# 2layer_v1.net
KiCad netlist of a schematic drawn in EAGLE
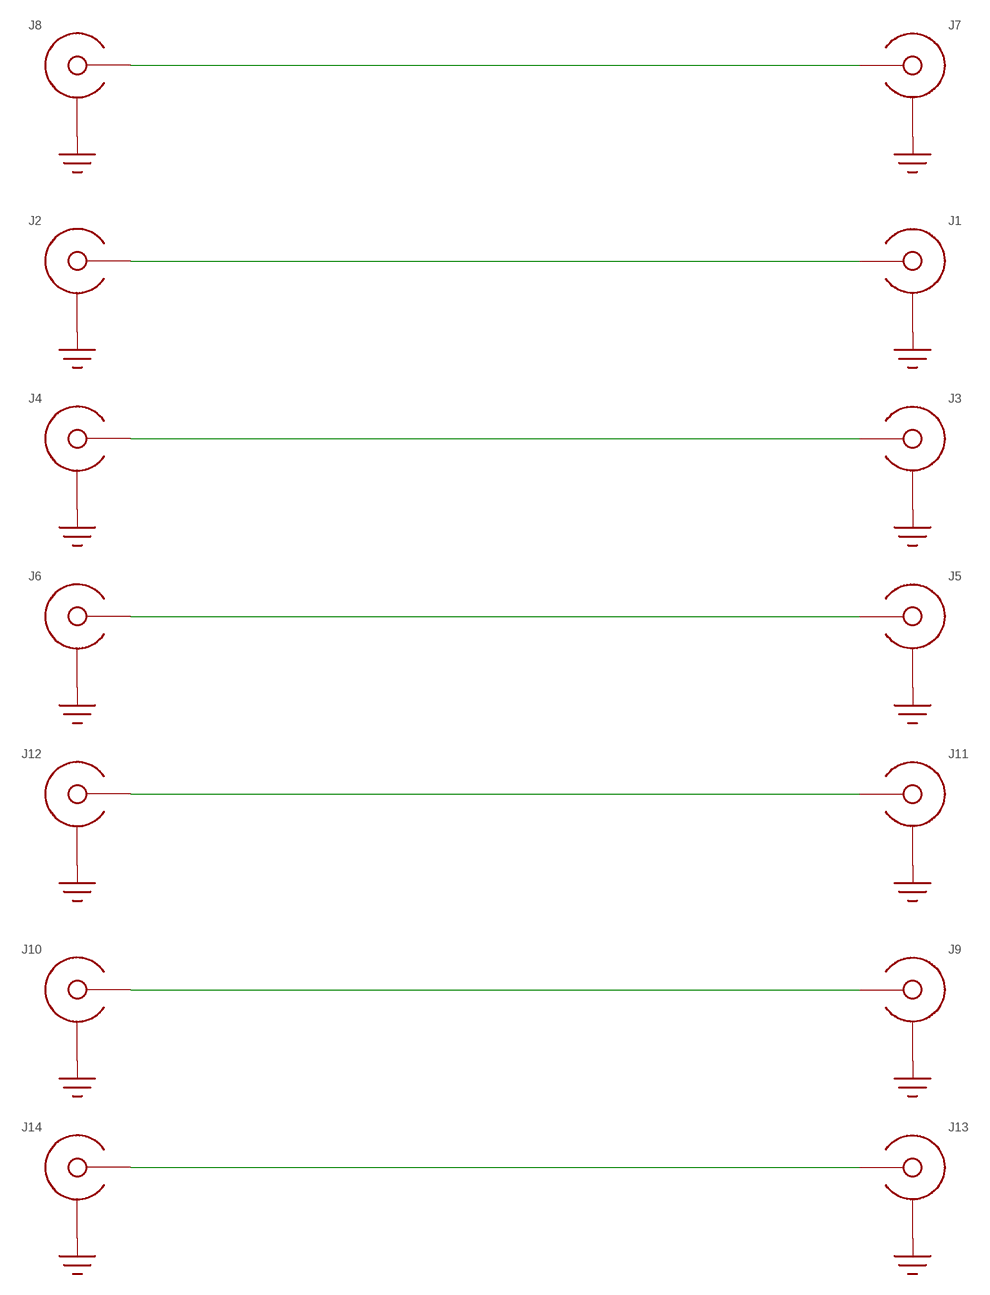
[diagram p0: schematic, sheet 1]

(export (version "E")
  (design (tool "Eeschema 10.0.6"))
  (components
    (comp (ref "J1")
      (value "SMA_END_LAUNCH2L")
      (footprint "eagle-import:SMA_EDGE_LAUNCH_2L")
      (libsource (lib "eagle-import") (part "SMA_END_LAUNCH2L"))
    )
    (comp (ref "J2")
      (value "SMA_END_LAUNCH2L")
      (footprint "eagle-import:SMA_EDGE_LAUNCH_2L")
      (libsource (lib "eagle-import") (part "SMA_END_LAUNCH2L"))
    )
    (comp (ref "J3")
      (value "SMA_END_LAUNCH2L")
      (footprint "eagle-import:SMA_EDGE_LAUNCH_2L")
      (libsource (lib "eagle-import") (part "SMA_END_LAUNCH2L"))
    )
    (comp (ref "J4")
      (value "SMA_END_LAUNCH2L")
      (footprint "eagle-import:SMA_EDGE_LAUNCH_2L")
      (libsource (lib "eagle-import") (part "SMA_END_LAUNCH2L"))
    )
    (comp (ref "J5")
      (value "SMA_END_LAUNCH2L")
      (footprint "eagle-import:SMA_EDGE_LAUNCH_2L")
      (libsource (lib "eagle-import") (part "SMA_END_LAUNCH2L"))
    )
    (comp (ref "J6")
      (value "SMA_END_LAUNCH2L")
      (footprint "eagle-import:SMA_EDGE_LAUNCH_2L")
      (libsource (lib "eagle-import") (part "SMA_END_LAUNCH2L"))
    )
    (comp (ref "J7")
      (value "SMA_END_LAUNCH2L")
      (footprint "eagle-import:SMA_EDGE_LAUNCH_2L")
      (libsource (lib "eagle-import") (part "SMA_END_LAUNCH2L"))
    )
    (comp (ref "J8")
      (value "SMA_END_LAUNCH2L")
      (footprint "eagle-import:SMA_EDGE_LAUNCH_2L")
      (libsource (lib "eagle-import") (part "SMA_END_LAUNCH2L"))
    )
    (comp (ref "J9")
      (value "SMA_END_LAUNCH2L")
      (footprint "eagle-import:SMA_EDGE_LAUNCH_2L")
      (libsource (lib "eagle-import") (part "SMA_END_LAUNCH2L"))
    )
    (comp (ref "J10")
      (value "SMA_END_LAUNCH2L")
      (footprint "eagle-import:SMA_EDGE_LAUNCH_2L")
      (libsource (lib "eagle-import") (part "SMA_END_LAUNCH2L"))
    )
    (comp (ref "J11")
      (value "SMA_END_LAUNCH2L")
      (footprint "eagle-import:SMA_EDGE_LAUNCH_2L")
      (libsource (lib "eagle-import") (part "SMA_END_LAUNCH2L"))
    )
    (comp (ref "J12")
      (value "SMA_END_LAUNCH2L")
      (footprint "eagle-import:SMA_EDGE_LAUNCH_2L")
      (libsource (lib "eagle-import") (part "SMA_END_LAUNCH2L"))
    )
    (comp (ref "J13")
      (value "SMA_END_LAUNCH2L")
      (footprint "eagle-import:SMA_EDGE_LAUNCH_2L")
      (libsource (lib "eagle-import") (part "SMA_END_LAUNCH2L"))
    )
    (comp (ref "J14")
      (value "SMA_END_LAUNCH2L")
      (footprint "eagle-import:SMA_EDGE_LAUNCH_2L")
      (libsource (lib "eagle-import") (part "SMA_END_LAUNCH2L"))
    )
  )
  (nets
    (net (code "1") (name "GND") (class "Default")
      (node (ref "J1") (pin "BOTTOM_GND") (pinfunction "SHIELD_BOTTOM_GND") (pintype "bidirectional"))
      (node (ref "J1") (pin "GND@1") (pinfunction "SHIELD_GND@1") (pintype "bidirectional"))
      (node (ref "J1") (pin "GND@11") (pinfunction "SHIELD_GND@11") (pintype "bidirectional"))
      (node (ref "J1") (pin "GND@12") (pinfunction "SHIELD_GND@12") (pintype "bidirectional"))
      (node (ref "J1") (pin "GND@14") (pinfunction "SHIELD_GND@14") (pintype "bidirectional"))
      (node (ref "J1") (pin "GND@15") (pinfunction "SHIELD_GND@15") (pintype "bidirectional"))
      (node (ref "J1") (pin "GND@16") (pinfunction "SHIELD_GND@16") (pintype "bidirectional"))
      (node (ref "J1") (pin "GND@17") (pinfunction "SHIELD_GND@17") (pintype "bidirectional"))
      (node (ref "J1") (pin "GND@2") (pinfunction "SHIELD_GND@2") (pintype "bidirectional"))
      (node (ref "J1") (pin "GND@3") (pinfunction "SHIELD_GND@3") (pintype "bidirectional"))
      (node (ref "J1") (pin "GND@4") (pinfunction "SHIELD_GND@4") (pintype "bidirectional"))
      (node (ref "J1") (pin "GND@5") (pinfunction "SHIELD_GND@5") (pintype "bidirectional"))
      (node (ref "J1") (pin "GND@6") (pinfunction "SHIELD_GND@6") (pintype "bidirectional"))
      (node (ref "J1") (pin "GND@7") (pinfunction "SHIELD_GND@7") (pintype "bidirectional"))
      (node (ref "J1") (pin "GND@8") (pinfunction "SHIELD_GND@8") (pintype "bidirectional"))
      (node (ref "J1") (pin "GND_PAD1") (pinfunction "SHIELD_GND_PAD1") (pintype "bidirectional"))
      (node (ref "J1") (pin "GND_PAD2") (pinfunction "SHIELD_GND_PAD2") (pintype "bidirectional"))
      (node (ref "J10") (pin "BOTTOM_GND") (pinfunction "SHIELD_BOTTOM_GND") (pintype "bidirectional"))
      (node (ref "J10") (pin "GND@1") (pinfunction "SHIELD_GND@1") (pintype "bidirectional"))
      (node (ref "J10") (pin "GND@11") (pinfunction "SHIELD_GND@11") (pintype "bidirectional"))
      (node (ref "J10") (pin "GND@12") (pinfunction "SHIELD_GND@12") (pintype "bidirectional"))
      (node (ref "J10") (pin "GND@14") (pinfunction "SHIELD_GND@14") (pintype "bidirectional"))
      (node (ref "J10") (pin "GND@15") (pinfunction "SHIELD_GND@15") (pintype "bidirectional"))
      (node (ref "J10") (pin "GND@16") (pinfunction "SHIELD_GND@16") (pintype "bidirectional"))
      (node (ref "J10") (pin "GND@17") (pinfunction "SHIELD_GND@17") (pintype "bidirectional"))
      (node (ref "J10") (pin "GND@2") (pinfunction "SHIELD_GND@2") (pintype "bidirectional"))
      (node (ref "J10") (pin "GND@3") (pinfunction "SHIELD_GND@3") (pintype "bidirectional"))
      (node (ref "J10") (pin "GND@4") (pinfunction "SHIELD_GND@4") (pintype "bidirectional"))
      (node (ref "J10") (pin "GND@5") (pinfunction "SHIELD_GND@5") (pintype "bidirectional"))
      (node (ref "J10") (pin "GND@6") (pinfunction "SHIELD_GND@6") (pintype "bidirectional"))
      (node (ref "J10") (pin "GND@7") (pinfunction "SHIELD_GND@7") (pintype "bidirectional"))
      (node (ref "J10") (pin "GND@8") (pinfunction "SHIELD_GND@8") (pintype "bidirectional"))
      (node (ref "J10") (pin "GND_PAD1") (pinfunction "SHIELD_GND_PAD1") (pintype "bidirectional"))
      (node (ref "J10") (pin "GND_PAD2") (pinfunction "SHIELD_GND_PAD2") (pintype "bidirectional"))
      (node (ref "J11") (pin "BOTTOM_GND") (pinfunction "SHIELD_BOTTOM_GND") (pintype "bidirectional"))
      (node (ref "J11") (pin "GND@1") (pinfunction "SHIELD_GND@1") (pintype "bidirectional"))
      (node (ref "J11") (pin "GND@11") (pinfunction "SHIELD_GND@11") (pintype "bidirectional"))
      (node (ref "J11") (pin "GND@12") (pinfunction "SHIELD_GND@12") (pintype "bidirectional"))
      (node (ref "J11") (pin "GND@14") (pinfunction "SHIELD_GND@14") (pintype "bidirectional"))
      (node (ref "J11") (pin "GND@15") (pinfunction "SHIELD_GND@15") (pintype "bidirectional"))
      (node (ref "J11") (pin "GND@16") (pinfunction "SHIELD_GND@16") (pintype "bidirectional"))
      (node (ref "J11") (pin "GND@17") (pinfunction "SHIELD_GND@17") (pintype "bidirectional"))
      (node (ref "J11") (pin "GND@2") (pinfunction "SHIELD_GND@2") (pintype "bidirectional"))
      (node (ref "J11") (pin "GND@3") (pinfunction "SHIELD_GND@3") (pintype "bidirectional"))
      (node (ref "J11") (pin "GND@4") (pinfunction "SHIELD_GND@4") (pintype "bidirectional"))
      (node (ref "J11") (pin "GND@5") (pinfunction "SHIELD_GND@5") (pintype "bidirectional"))
      (node (ref "J11") (pin "GND@6") (pinfunction "SHIELD_GND@6") (pintype "bidirectional"))
      (node (ref "J11") (pin "GND@7") (pinfunction "SHIELD_GND@7") (pintype "bidirectional"))
      (node (ref "J11") (pin "GND@8") (pinfunction "SHIELD_GND@8") (pintype "bidirectional"))
      (node (ref "J11") (pin "GND_PAD1") (pinfunction "SHIELD_GND_PAD1") (pintype "bidirectional"))
      (node (ref "J11") (pin "GND_PAD2") (pinfunction "SHIELD_GND_PAD2") (pintype "bidirectional"))
      (node (ref "J12") (pin "BOTTOM_GND") (pinfunction "SHIELD_BOTTOM_GND") (pintype "bidirectional"))
      (node (ref "J12") (pin "GND@1") (pinfunction "SHIELD_GND@1") (pintype "bidirectional"))
      (node (ref "J12") (pin "GND@11") (pinfunction "SHIELD_GND@11") (pintype "bidirectional"))
      (node (ref "J12") (pin "GND@12") (pinfunction "SHIELD_GND@12") (pintype "bidirectional"))
      (node (ref "J12") (pin "GND@14") (pinfunction "SHIELD_GND@14") (pintype "bidirectional"))
      (node (ref "J12") (pin "GND@15") (pinfunction "SHIELD_GND@15") (pintype "bidirectional"))
      (node (ref "J12") (pin "GND@16") (pinfunction "SHIELD_GND@16") (pintype "bidirectional"))
      (node (ref "J12") (pin "GND@17") (pinfunction "SHIELD_GND@17") (pintype "bidirectional"))
      (node (ref "J12") (pin "GND@2") (pinfunction "SHIELD_GND@2") (pintype "bidirectional"))
      (node (ref "J12") (pin "GND@3") (pinfunction "SHIELD_GND@3") (pintype "bidirectional"))
      (node (ref "J12") (pin "GND@4") (pinfunction "SHIELD_GND@4") (pintype "bidirectional"))
      (node (ref "J12") (pin "GND@5") (pinfunction "SHIELD_GND@5") (pintype "bidirectional"))
      (node (ref "J12") (pin "GND@6") (pinfunction "SHIELD_GND@6") (pintype "bidirectional"))
      (node (ref "J12") (pin "GND@7") (pinfunction "SHIELD_GND@7") (pintype "bidirectional"))
      (node (ref "J12") (pin "GND@8") (pinfunction "SHIELD_GND@8") (pintype "bidirectional"))
      (node (ref "J12") (pin "GND_PAD1") (pinfunction "SHIELD_GND_PAD1") (pintype "bidirectional"))
      (node (ref "J12") (pin "GND_PAD2") (pinfunction "SHIELD_GND_PAD2") (pintype "bidirectional"))
      (node (ref "J13") (pin "BOTTOM_GND") (pinfunction "SHIELD_BOTTOM_GND") (pintype "bidirectional"))
      (node (ref "J13") (pin "GND@1") (pinfunction "SHIELD_GND@1") (pintype "bidirectional"))
      (node (ref "J13") (pin "GND@11") (pinfunction "SHIELD_GND@11") (pintype "bidirectional"))
      (node (ref "J13") (pin "GND@12") (pinfunction "SHIELD_GND@12") (pintype "bidirectional"))
      (node (ref "J13") (pin "GND@14") (pinfunction "SHIELD_GND@14") (pintype "bidirectional"))
      (node (ref "J13") (pin "GND@15") (pinfunction "SHIELD_GND@15") (pintype "bidirectional"))
      (node (ref "J13") (pin "GND@16") (pinfunction "SHIELD_GND@16") (pintype "bidirectional"))
      (node (ref "J13") (pin "GND@17") (pinfunction "SHIELD_GND@17") (pintype "bidirectional"))
      (node (ref "J13") (pin "GND@2") (pinfunction "SHIELD_GND@2") (pintype "bidirectional"))
      (node (ref "J13") (pin "GND@3") (pinfunction "SHIELD_GND@3") (pintype "bidirectional"))
      (node (ref "J13") (pin "GND@4") (pinfunction "SHIELD_GND@4") (pintype "bidirectional"))
      (node (ref "J13") (pin "GND@5") (pinfunction "SHIELD_GND@5") (pintype "bidirectional"))
      (node (ref "J13") (pin "GND@6") (pinfunction "SHIELD_GND@6") (pintype "bidirectional"))
      (node (ref "J13") (pin "GND@7") (pinfunction "SHIELD_GND@7") (pintype "bidirectional"))
      (node (ref "J13") (pin "GND@8") (pinfunction "SHIELD_GND@8") (pintype "bidirectional"))
      (node (ref "J13") (pin "GND_PAD1") (pinfunction "SHIELD_GND_PAD1") (pintype "bidirectional"))
      (node (ref "J13") (pin "GND_PAD2") (pinfunction "SHIELD_GND_PAD2") (pintype "bidirectional"))
      (node (ref "J14") (pin "BOTTOM_GND") (pinfunction "SHIELD_BOTTOM_GND") (pintype "bidirectional"))
      (node (ref "J14") (pin "GND@1") (pinfunction "SHIELD_GND@1") (pintype "bidirectional"))
      (node (ref "J14") (pin "GND@11") (pinfunction "SHIELD_GND@11") (pintype "bidirectional"))
      (node (ref "J14") (pin "GND@12") (pinfunction "SHIELD_GND@12") (pintype "bidirectional"))
      (node (ref "J14") (pin "GND@14") (pinfunction "SHIELD_GND@14") (pintype "bidirectional"))
      (node (ref "J14") (pin "GND@15") (pinfunction "SHIELD_GND@15") (pintype "bidirectional"))
      (node (ref "J14") (pin "GND@16") (pinfunction "SHIELD_GND@16") (pintype "bidirectional"))
      (node (ref "J14") (pin "GND@17") (pinfunction "SHIELD_GND@17") (pintype "bidirectional"))
      (node (ref "J14") (pin "GND@2") (pinfunction "SHIELD_GND@2") (pintype "bidirectional"))
      (node (ref "J14") (pin "GND@3") (pinfunction "SHIELD_GND@3") (pintype "bidirectional"))
      (node (ref "J14") (pin "GND@4") (pinfunction "SHIELD_GND@4") (pintype "bidirectional"))
      (node (ref "J14") (pin "GND@5") (pinfunction "SHIELD_GND@5") (pintype "bidirectional"))
      (node (ref "J14") (pin "GND@6") (pinfunction "SHIELD_GND@6") (pintype "bidirectional"))
      (node (ref "J14") (pin "GND@7") (pinfunction "SHIELD_GND@7") (pintype "bidirectional"))
      (node (ref "J14") (pin "GND@8") (pinfunction "SHIELD_GND@8") (pintype "bidirectional"))
      (node (ref "J14") (pin "GND_PAD1") (pinfunction "SHIELD_GND_PAD1") (pintype "bidirectional"))
      (node (ref "J14") (pin "GND_PAD2") (pinfunction "SHIELD_GND_PAD2") (pintype "bidirectional"))
      (node (ref "J2") (pin "BOTTOM_GND") (pinfunction "SHIELD_BOTTOM_GND") (pintype "bidirectional"))
      (node (ref "J2") (pin "GND@1") (pinfunction "SHIELD_GND@1") (pintype "bidirectional"))
      (node (ref "J2") (pin "GND@11") (pinfunction "SHIELD_GND@11") (pintype "bidirectional"))
      (node (ref "J2") (pin "GND@12") (pinfunction "SHIELD_GND@12") (pintype "bidirectional"))
      (node (ref "J2") (pin "GND@14") (pinfunction "SHIELD_GND@14") (pintype "bidirectional"))
      (node (ref "J2") (pin "GND@15") (pinfunction "SHIELD_GND@15") (pintype "bidirectional"))
      (node (ref "J2") (pin "GND@16") (pinfunction "SHIELD_GND@16") (pintype "bidirectional"))
      (node (ref "J2") (pin "GND@17") (pinfunction "SHIELD_GND@17") (pintype "bidirectional"))
      (node (ref "J2") (pin "GND@2") (pinfunction "SHIELD_GND@2") (pintype "bidirectional"))
      (node (ref "J2") (pin "GND@3") (pinfunction "SHIELD_GND@3") (pintype "bidirectional"))
      (node (ref "J2") (pin "GND@4") (pinfunction "SHIELD_GND@4") (pintype "bidirectional"))
      (node (ref "J2") (pin "GND@5") (pinfunction "SHIELD_GND@5") (pintype "bidirectional"))
      (node (ref "J2") (pin "GND@6") (pinfunction "SHIELD_GND@6") (pintype "bidirectional"))
      (node (ref "J2") (pin "GND@7") (pinfunction "SHIELD_GND@7") (pintype "bidirectional"))
      (node (ref "J2") (pin "GND@8") (pinfunction "SHIELD_GND@8") (pintype "bidirectional"))
      (node (ref "J2") (pin "GND_PAD1") (pinfunction "SHIELD_GND_PAD1") (pintype "bidirectional"))
      (node (ref "J2") (pin "GND_PAD2") (pinfunction "SHIELD_GND_PAD2") (pintype "bidirectional"))
      (node (ref "J3") (pin "BOTTOM_GND") (pinfunction "SHIELD_BOTTOM_GND") (pintype "bidirectional"))
      (node (ref "J3") (pin "GND@1") (pinfunction "SHIELD_GND@1") (pintype "bidirectional"))
      (node (ref "J3") (pin "GND@11") (pinfunction "SHIELD_GND@11") (pintype "bidirectional"))
      (node (ref "J3") (pin "GND@12") (pinfunction "SHIELD_GND@12") (pintype "bidirectional"))
      (node (ref "J3") (pin "GND@14") (pinfunction "SHIELD_GND@14") (pintype "bidirectional"))
      (node (ref "J3") (pin "GND@15") (pinfunction "SHIELD_GND@15") (pintype "bidirectional"))
      (node (ref "J3") (pin "GND@16") (pinfunction "SHIELD_GND@16") (pintype "bidirectional"))
      (node (ref "J3") (pin "GND@17") (pinfunction "SHIELD_GND@17") (pintype "bidirectional"))
      (node (ref "J3") (pin "GND@2") (pinfunction "SHIELD_GND@2") (pintype "bidirectional"))
      (node (ref "J3") (pin "GND@3") (pinfunction "SHIELD_GND@3") (pintype "bidirectional"))
      (node (ref "J3") (pin "GND@4") (pinfunction "SHIELD_GND@4") (pintype "bidirectional"))
      (node (ref "J3") (pin "GND@5") (pinfunction "SHIELD_GND@5") (pintype "bidirectional"))
      (node (ref "J3") (pin "GND@6") (pinfunction "SHIELD_GND@6") (pintype "bidirectional"))
      (node (ref "J3") (pin "GND@7") (pinfunction "SHIELD_GND@7") (pintype "bidirectional"))
      (node (ref "J3") (pin "GND@8") (pinfunction "SHIELD_GND@8") (pintype "bidirectional"))
      (node (ref "J3") (pin "GND_PAD1") (pinfunction "SHIELD_GND_PAD1") (pintype "bidirectional"))
      (node (ref "J3") (pin "GND_PAD2") (pinfunction "SHIELD_GND_PAD2") (pintype "bidirectional"))
      (node (ref "J4") (pin "BOTTOM_GND") (pinfunction "SHIELD_BOTTOM_GND") (pintype "bidirectional"))
      (node (ref "J4") (pin "GND@1") (pinfunction "SHIELD_GND@1") (pintype "bidirectional"))
      (node (ref "J4") (pin "GND@11") (pinfunction "SHIELD_GND@11") (pintype "bidirectional"))
      (node (ref "J4") (pin "GND@12") (pinfunction "SHIELD_GND@12") (pintype "bidirectional"))
      (node (ref "J4") (pin "GND@14") (pinfunction "SHIELD_GND@14") (pintype "bidirectional"))
      (node (ref "J4") (pin "GND@15") (pinfunction "SHIELD_GND@15") (pintype "bidirectional"))
      (node (ref "J4") (pin "GND@16") (pinfunction "SHIELD_GND@16") (pintype "bidirectional"))
      (node (ref "J4") (pin "GND@17") (pinfunction "SHIELD_GND@17") (pintype "bidirectional"))
      (node (ref "J4") (pin "GND@2") (pinfunction "SHIELD_GND@2") (pintype "bidirectional"))
      (node (ref "J4") (pin "GND@3") (pinfunction "SHIELD_GND@3") (pintype "bidirectional"))
      (node (ref "J4") (pin "GND@4") (pinfunction "SHIELD_GND@4") (pintype "bidirectional"))
      (node (ref "J4") (pin "GND@5") (pinfunction "SHIELD_GND@5") (pintype "bidirectional"))
      (node (ref "J4") (pin "GND@6") (pinfunction "SHIELD_GND@6") (pintype "bidirectional"))
      (node (ref "J4") (pin "GND@7") (pinfunction "SHIELD_GND@7") (pintype "bidirectional"))
      (node (ref "J4") (pin "GND@8") (pinfunction "SHIELD_GND@8") (pintype "bidirectional"))
      (node (ref "J4") (pin "GND_PAD1") (pinfunction "SHIELD_GND_PAD1") (pintype "bidirectional"))
      (node (ref "J4") (pin "GND_PAD2") (pinfunction "SHIELD_GND_PAD2") (pintype "bidirectional"))
      (node (ref "J5") (pin "BOTTOM_GND") (pinfunction "SHIELD_BOTTOM_GND") (pintype "bidirectional"))
      (node (ref "J5") (pin "GND@1") (pinfunction "SHIELD_GND@1") (pintype "bidirectional"))
      (node (ref "J5") (pin "GND@11") (pinfunction "SHIELD_GND@11") (pintype "bidirectional"))
      (node (ref "J5") (pin "GND@12") (pinfunction "SHIELD_GND@12") (pintype "bidirectional"))
      (node (ref "J5") (pin "GND@14") (pinfunction "SHIELD_GND@14") (pintype "bidirectional"))
      (node (ref "J5") (pin "GND@15") (pinfunction "SHIELD_GND@15") (pintype "bidirectional"))
      (node (ref "J5") (pin "GND@16") (pinfunction "SHIELD_GND@16") (pintype "bidirectional"))
      (node (ref "J5") (pin "GND@17") (pinfunction "SHIELD_GND@17") (pintype "bidirectional"))
      (node (ref "J5") (pin "GND@2") (pinfunction "SHIELD_GND@2") (pintype "bidirectional"))
      (node (ref "J5") (pin "GND@3") (pinfunction "SHIELD_GND@3") (pintype "bidirectional"))
      (node (ref "J5") (pin "GND@4") (pinfunction "SHIELD_GND@4") (pintype "bidirectional"))
      (node (ref "J5") (pin "GND@5") (pinfunction "SHIELD_GND@5") (pintype "bidirectional"))
      (node (ref "J5") (pin "GND@6") (pinfunction "SHIELD_GND@6") (pintype "bidirectional"))
      (node (ref "J5") (pin "GND@7") (pinfunction "SHIELD_GND@7") (pintype "bidirectional"))
      (node (ref "J5") (pin "GND@8") (pinfunction "SHIELD_GND@8") (pintype "bidirectional"))
      (node (ref "J5") (pin "GND_PAD1") (pinfunction "SHIELD_GND_PAD1") (pintype "bidirectional"))
      (node (ref "J5") (pin "GND_PAD2") (pinfunction "SHIELD_GND_PAD2") (pintype "bidirectional"))
      (node (ref "J6") (pin "BOTTOM_GND") (pinfunction "SHIELD_BOTTOM_GND") (pintype "bidirectional"))
      (node (ref "J6") (pin "GND@1") (pinfunction "SHIELD_GND@1") (pintype "bidirectional"))
      (node (ref "J6") (pin "GND@11") (pinfunction "SHIELD_GND@11") (pintype "bidirectional"))
      (node (ref "J6") (pin "GND@12") (pinfunction "SHIELD_GND@12") (pintype "bidirectional"))
      (node (ref "J6") (pin "GND@14") (pinfunction "SHIELD_GND@14") (pintype "bidirectional"))
      (node (ref "J6") (pin "GND@15") (pinfunction "SHIELD_GND@15") (pintype "bidirectional"))
      (node (ref "J6") (pin "GND@16") (pinfunction "SHIELD_GND@16") (pintype "bidirectional"))
      (node (ref "J6") (pin "GND@17") (pinfunction "SHIELD_GND@17") (pintype "bidirectional"))
      (node (ref "J6") (pin "GND@2") (pinfunction "SHIELD_GND@2") (pintype "bidirectional"))
      (node (ref "J6") (pin "GND@3") (pinfunction "SHIELD_GND@3") (pintype "bidirectional"))
      (node (ref "J6") (pin "GND@4") (pinfunction "SHIELD_GND@4") (pintype "bidirectional"))
      (node (ref "J6") (pin "GND@5") (pinfunction "SHIELD_GND@5") (pintype "bidirectional"))
      (node (ref "J6") (pin "GND@6") (pinfunction "SHIELD_GND@6") (pintype "bidirectional"))
      (node (ref "J6") (pin "GND@7") (pinfunction "SHIELD_GND@7") (pintype "bidirectional"))
      (node (ref "J6") (pin "GND@8") (pinfunction "SHIELD_GND@8") (pintype "bidirectional"))
      (node (ref "J6") (pin "GND_PAD1") (pinfunction "SHIELD_GND_PAD1") (pintype "bidirectional"))
      (node (ref "J6") (pin "GND_PAD2") (pinfunction "SHIELD_GND_PAD2") (pintype "bidirectional"))
      (node (ref "J7") (pin "BOTTOM_GND") (pinfunction "SHIELD_BOTTOM_GND") (pintype "bidirectional"))
      (node (ref "J7") (pin "GND@1") (pinfunction "SHIELD_GND@1") (pintype "bidirectional"))
      (node (ref "J7") (pin "GND@11") (pinfunction "SHIELD_GND@11") (pintype "bidirectional"))
      (node (ref "J7") (pin "GND@12") (pinfunction "SHIELD_GND@12") (pintype "bidirectional"))
      (node (ref "J7") (pin "GND@14") (pinfunction "SHIELD_GND@14") (pintype "bidirectional"))
      (node (ref "J7") (pin "GND@15") (pinfunction "SHIELD_GND@15") (pintype "bidirectional"))
      (node (ref "J7") (pin "GND@16") (pinfunction "SHIELD_GND@16") (pintype "bidirectional"))
      (node (ref "J7") (pin "GND@17") (pinfunction "SHIELD_GND@17") (pintype "bidirectional"))
      (node (ref "J7") (pin "GND@2") (pinfunction "SHIELD_GND@2") (pintype "bidirectional"))
      (node (ref "J7") (pin "GND@3") (pinfunction "SHIELD_GND@3") (pintype "bidirectional"))
      (node (ref "J7") (pin "GND@4") (pinfunction "SHIELD_GND@4") (pintype "bidirectional"))
      (node (ref "J7") (pin "GND@5") (pinfunction "SHIELD_GND@5") (pintype "bidirectional"))
      (node (ref "J7") (pin "GND@6") (pinfunction "SHIELD_GND@6") (pintype "bidirectional"))
      (node (ref "J7") (pin "GND@7") (pinfunction "SHIELD_GND@7") (pintype "bidirectional"))
      (node (ref "J7") (pin "GND@8") (pinfunction "SHIELD_GND@8") (pintype "bidirectional"))
      (node (ref "J7") (pin "GND_PAD1") (pinfunction "SHIELD_GND_PAD1") (pintype "bidirectional"))
      (node (ref "J7") (pin "GND_PAD2") (pinfunction "SHIELD_GND_PAD2") (pintype "bidirectional"))
      (node (ref "J8") (pin "BOTTOM_GND") (pinfunction "SHIELD_BOTTOM_GND") (pintype "bidirectional"))
      (node (ref "J8") (pin "GND@1") (pinfunction "SHIELD_GND@1") (pintype "bidirectional"))
      (node (ref "J8") (pin "GND@11") (pinfunction "SHIELD_GND@11") (pintype "bidirectional"))
      (node (ref "J8") (pin "GND@12") (pinfunction "SHIELD_GND@12") (pintype "bidirectional"))
      (node (ref "J8") (pin "GND@14") (pinfunction "SHIELD_GND@14") (pintype "bidirectional"))
      (node (ref "J8") (pin "GND@15") (pinfunction "SHIELD_GND@15") (pintype "bidirectional"))
      (node (ref "J8") (pin "GND@16") (pinfunction "SHIELD_GND@16") (pintype "bidirectional"))
      (node (ref "J8") (pin "GND@17") (pinfunction "SHIELD_GND@17") (pintype "bidirectional"))
      (node (ref "J8") (pin "GND@2") (pinfunction "SHIELD_GND@2") (pintype "bidirectional"))
      (node (ref "J8") (pin "GND@3") (pinfunction "SHIELD_GND@3") (pintype "bidirectional"))
      (node (ref "J8") (pin "GND@4") (pinfunction "SHIELD_GND@4") (pintype "bidirectional"))
      (node (ref "J8") (pin "GND@5") (pinfunction "SHIELD_GND@5") (pintype "bidirectional"))
      (node (ref "J8") (pin "GND@6") (pinfunction "SHIELD_GND@6") (pintype "bidirectional"))
      (node (ref "J8") (pin "GND@7") (pinfunction "SHIELD_GND@7") (pintype "bidirectional"))
      (node (ref "J8") (pin "GND@8") (pinfunction "SHIELD_GND@8") (pintype "bidirectional"))
      (node (ref "J8") (pin "GND_PAD1") (pinfunction "SHIELD_GND_PAD1") (pintype "bidirectional"))
      (node (ref "J8") (pin "GND_PAD2") (pinfunction "SHIELD_GND_PAD2") (pintype "bidirectional"))
      (node (ref "J9") (pin "BOTTOM_GND") (pinfunction "SHIELD_BOTTOM_GND") (pintype "bidirectional"))
      (node (ref "J9") (pin "GND@1") (pinfunction "SHIELD_GND@1") (pintype "bidirectional"))
      (node (ref "J9") (pin "GND@11") (pinfunction "SHIELD_GND@11") (pintype "bidirectional"))
      (node (ref "J9") (pin "GND@12") (pinfunction "SHIELD_GND@12") (pintype "bidirectional"))
      (node (ref "J9") (pin "GND@14") (pinfunction "SHIELD_GND@14") (pintype "bidirectional"))
      (node (ref "J9") (pin "GND@15") (pinfunction "SHIELD_GND@15") (pintype "bidirectional"))
      (node (ref "J9") (pin "GND@16") (pinfunction "SHIELD_GND@16") (pintype "bidirectional"))
      (node (ref "J9") (pin "GND@17") (pinfunction "SHIELD_GND@17") (pintype "bidirectional"))
      (node (ref "J9") (pin "GND@2") (pinfunction "SHIELD_GND@2") (pintype "bidirectional"))
      (node (ref "J9") (pin "GND@3") (pinfunction "SHIELD_GND@3") (pintype "bidirectional"))
      (node (ref "J9") (pin "GND@4") (pinfunction "SHIELD_GND@4") (pintype "bidirectional"))
      (node (ref "J9") (pin "GND@5") (pinfunction "SHIELD_GND@5") (pintype "bidirectional"))
      (node (ref "J9") (pin "GND@6") (pinfunction "SHIELD_GND@6") (pintype "bidirectional"))
      (node (ref "J9") (pin "GND@7") (pinfunction "SHIELD_GND@7") (pintype "bidirectional"))
      (node (ref "J9") (pin "GND@8") (pinfunction "SHIELD_GND@8") (pintype "bidirectional"))
      (node (ref "J9") (pin "GND_PAD1") (pinfunction "SHIELD_GND_PAD1") (pintype "bidirectional"))
      (node (ref "J9") (pin "GND_PAD2") (pinfunction "SHIELD_GND_PAD2") (pintype "bidirectional"))
    )
    (net (code "2") (name "Net-(J1-CENTER)") (class "Default")
      (node (ref "J1") (pin "CENTER@1") (pinfunction "CENTER_CENTER@1") (pintype "bidirectional"))
      (node (ref "J2") (pin "CENTER@1") (pinfunction "CENTER_CENTER@1") (pintype "bidirectional"))
    )
    (net (code "3") (name "Net-(J3-CENTER)") (class "Default")
      (node (ref "J3") (pin "CENTER@1") (pinfunction "CENTER_CENTER@1") (pintype "bidirectional"))
      (node (ref "J4") (pin "CENTER@1") (pinfunction "CENTER_CENTER@1") (pintype "bidirectional"))
    )
    (net (code "4") (name "Net-(J5-CENTER)") (class "Default")
      (node (ref "J5") (pin "CENTER@1") (pinfunction "CENTER_CENTER@1") (pintype "bidirectional"))
      (node (ref "J6") (pin "CENTER@1") (pinfunction "CENTER_CENTER@1") (pintype "bidirectional"))
    )
    (net (code "5") (name "Net-(J7-CENTER)") (class "Default")
      (node (ref "J7") (pin "CENTER@1") (pinfunction "CENTER_CENTER@1") (pintype "bidirectional"))
      (node (ref "J8") (pin "CENTER@1") (pinfunction "CENTER_CENTER@1") (pintype "bidirectional"))
    )
    (net (code "6") (name "Net-(J10-CENTER)") (class "Default")
      (node (ref "J10") (pin "CENTER@1") (pinfunction "CENTER_CENTER@1") (pintype "bidirectional"))
      (node (ref "J9") (pin "CENTER@1") (pinfunction "CENTER_CENTER@1") (pintype "bidirectional"))
    )
    (net (code "7") (name "Net-(J11-CENTER)") (class "Default")
      (node (ref "J11") (pin "CENTER@1") (pinfunction "CENTER_CENTER@1") (pintype "bidirectional"))
      (node (ref "J12") (pin "CENTER@1") (pinfunction "CENTER_CENTER@1") (pintype "bidirectional"))
    )
    (net (code "8") (name "Net-(J13-CENTER)") (class "Default")
      (node (ref "J13") (pin "CENTER@1") (pinfunction "CENTER_CENTER@1") (pintype "bidirectional"))
      (node (ref "J14") (pin "CENTER@1") (pinfunction "CENTER_CENTER@1") (pintype "bidirectional"))
    )
  )
)
